# Input_Sequencer_Thing.net
KiCad netlist of a schematic drawn in EAGLE
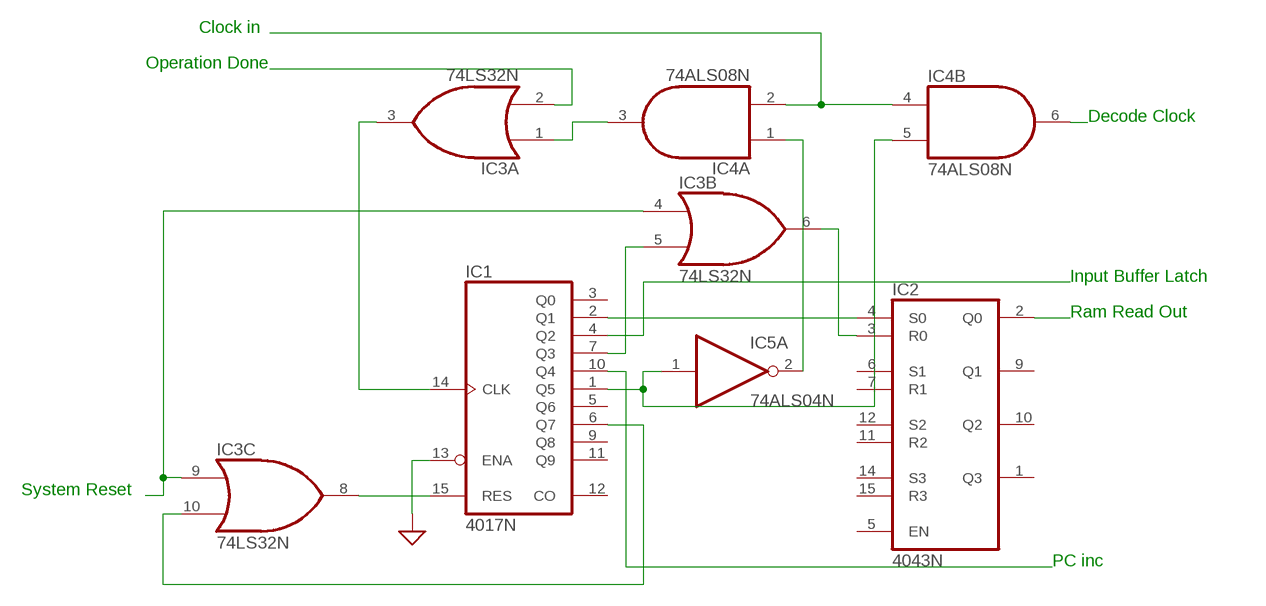
[diagram p0: schematic, sheet 1]

(export (version "E")
  (design (tool "Eeschema 10.0.6"))
  (components
    (comp (ref "IC1")
      (value "4017N")
      (footprint "eagle-import:DIL16")
      (libsource (lib "eagle-import") (part "4017N"))
    )
    (comp (ref "IC2")
      (value "4043N")
      (footprint "eagle-import:DIL16")
      (libsource (lib "eagle-import") (part "4043N"))
    )
    (comp (ref "IC3")
      (value "74LS32N")
      (footprint "eagle-import:DIL14")
      (libsource (lib "eagle-import") (part "7432NLS"))
    )
    (comp (ref "IC4")
      (value "74ALS08N")
      (footprint "eagle-import:DIL14")
      (libsource (lib "eagle-import") (part "7408NALS"))
    )
    (comp (ref "IC5")
      (value "74ALS04N")
      (footprint "eagle-import:DIL14")
      (libsource (lib "eagle-import") (part "7404NALS"))
    )
  )
  (nets
    (net (code "1") (name "Net-(IC1A-CLK)") (class "Default")
      (node (ref "IC1") (pin "14") (pinfunction "CLK_14") (pintype "input"))
      (node (ref "IC3") (pin "3") (pinfunction "O_3") (pintype "output"))
    )
    (net (code "2") (name "Net-(IC1A-Q1)") (class "Default")
      (node (ref "IC1") (pin "2") (pinfunction "Q1_2") (pintype "output"))
      (node (ref "IC2") (pin "4") (pinfunction "S0_4") (pintype "input"))
    )
    (net (code "3") (name "Net-(IC1A-Q3)") (class "Default")
      (node (ref "IC1") (pin "7") (pinfunction "Q3_7") (pintype "output"))
      (node (ref "IC3") (pin "5") (pinfunction "I1_5") (pintype "input"))
    )
    (net (code "4") (name "Net-(IC1A-Q5)") (class "Default")
      (node (ref "IC1") (pin "1") (pinfunction "Q5_1") (pintype "output"))
      (node (ref "IC4") (pin "5") (pinfunction "I1_5") (pintype "input"))
      (node (ref "IC5") (pin "1") (pinfunction "I_1") (pintype "input"))
    )
    (net (code "5") (name "Net-(IC1A-Q7)") (class "Default")
      (node (ref "IC1") (pin "6") (pinfunction "Q7_6") (pintype "output"))
      (node (ref "IC3") (pin "10") (pinfunction "I1_10") (pintype "input"))
    )
    (net (code "6") (name "Net-(IC1A-RES)") (class "Default")
      (node (ref "IC1") (pin "15") (pinfunction "RES_15") (pintype "input"))
      (node (ref "IC3") (pin "8") (pinfunction "O_8") (pintype "output"))
    )
    (net (code "7") (name "Net-(IC2A-R0)") (class "Default")
      (node (ref "IC2") (pin "3") (pinfunction "R0_3") (pintype "input"))
      (node (ref "IC3") (pin "6") (pinfunction "O_6") (pintype "output"))
    )
    (net (code "8") (name "Net-(IC3A-I0)") (class "Default")
      (node (ref "IC3") (pin "1") (pinfunction "I0_1") (pintype "input"))
      (node (ref "IC4") (pin "3") (pinfunction "O_3") (pintype "output"))
    )
    (net (code "9") (name "Net-(IC3B-I0)") (class "Default")
      (node (ref "IC3") (pin "4") (pinfunction "I0_4") (pintype "input"))
      (node (ref "IC3") (pin "9") (pinfunction "I0_9") (pintype "input"))
    )
    (net (code "10") (name "Net-(IC4A-I0)") (class "Default")
      (node (ref "IC4") (pin "1") (pinfunction "I0_1") (pintype "input"))
      (node (ref "IC5") (pin "2") (pinfunction "O_2") (pintype "output"))
    )
    (net (code "11") (name "Net-(IC4A-I1)") (class "Default")
      (node (ref "IC4") (pin "2") (pinfunction "I1_2") (pintype "input"))
      (node (ref "IC4") (pin "4") (pinfunction "I0_4") (pintype "input"))
    )
    (net (code "12") (name "SUP") (class "Default")
      (node (ref "IC1") (pin "13") (pinfunction "ENA_13") (pintype "input"))
    )
    (net (code "13") (name "unconnected-(IC1A-CO-Pad12)") (class "Default")
      (node (ref "IC1") (pin "12") (pinfunction "CO_12") (pintype "output"))
    )
    (net (code "14") (name "unconnected-(IC1A-Q0-Pad3)") (class "Default")
      (node (ref "IC1") (pin "3") (pinfunction "Q0_3") (pintype "output"))
    )
    (net (code "15") (name "unconnected-(IC1A-Q2-Pad4)") (class "Default")
      (node (ref "IC1") (pin "4") (pinfunction "Q2_4") (pintype "output"))
    )
    (net (code "16") (name "unconnected-(IC1A-Q4-Pad10)") (class "Default")
      (node (ref "IC1") (pin "10") (pinfunction "Q4_10") (pintype "output"))
    )
    (net (code "17") (name "unconnected-(IC1A-Q6-Pad5)") (class "Default")
      (node (ref "IC1") (pin "5") (pinfunction "Q6_5") (pintype "output"))
    )
    (net (code "18") (name "unconnected-(IC1A-Q8-Pad9)") (class "Default")
      (node (ref "IC1") (pin "9") (pinfunction "Q8_9") (pintype "output"))
    )
    (net (code "19") (name "unconnected-(IC1A-Q9-Pad11)") (class "Default")
      (node (ref "IC1") (pin "11") (pinfunction "Q9_11") (pintype "output"))
    )
    (net (code "20") (name "unconnected-(IC2A-EN-Pad5)") (class "Default")
      (node (ref "IC2") (pin "5") (pinfunction "EN_5") (pintype "input"))
    )
    (net (code "21") (name "unconnected-(IC2A-Q0-Pad2)") (class "Default")
      (node (ref "IC2") (pin "2") (pinfunction "Q0_2") (pintype "output"))
    )
    (net (code "22") (name "unconnected-(IC2A-Q1-Pad9)") (class "Default")
      (node (ref "IC2") (pin "9") (pinfunction "Q1_9") (pintype "output"))
    )
    (net (code "23") (name "unconnected-(IC2A-Q2-Pad10)") (class "Default")
      (node (ref "IC2") (pin "10") (pinfunction "Q2_10") (pintype "output"))
    )
    (net (code "24") (name "unconnected-(IC2A-Q3-Pad1)") (class "Default")
      (node (ref "IC2") (pin "1") (pinfunction "Q3_1") (pintype "output"))
    )
    (net (code "25") (name "unconnected-(IC2A-R1-Pad7)") (class "Default")
      (node (ref "IC2") (pin "7") (pinfunction "R1_7") (pintype "input"))
    )
    (net (code "26") (name "unconnected-(IC2A-R2-Pad11)") (class "Default")
      (node (ref "IC2") (pin "11") (pinfunction "R2_11") (pintype "input"))
    )
    (net (code "27") (name "unconnected-(IC2A-R3-Pad15)") (class "Default")
      (node (ref "IC2") (pin "15") (pinfunction "R3_15") (pintype "input"))
    )
    (net (code "28") (name "unconnected-(IC2A-S1-Pad6)") (class "Default")
      (node (ref "IC2") (pin "6") (pinfunction "S1_6") (pintype "input"))
    )
    (net (code "29") (name "unconnected-(IC2A-S2-Pad12)") (class "Default")
      (node (ref "IC2") (pin "12") (pinfunction "S2_12") (pintype "input"))
    )
    (net (code "30") (name "unconnected-(IC2A-S3-Pad14)") (class "Default")
      (node (ref "IC2") (pin "14") (pinfunction "S3_14") (pintype "input"))
    )
    (net (code "31") (name "unconnected-(IC3A-I1-Pad2)") (class "Default")
      (node (ref "IC3") (pin "2") (pinfunction "I1_2") (pintype "input"))
    )
    (net (code "32") (name "unconnected-(IC4B-O-Pad6)") (class "Default")
      (node (ref "IC4") (pin "6") (pinfunction "O_6") (pintype "output"))
    )
  )
)
